# mainV2b.net
KiCad netlist of a schematic drawn in EAGLE
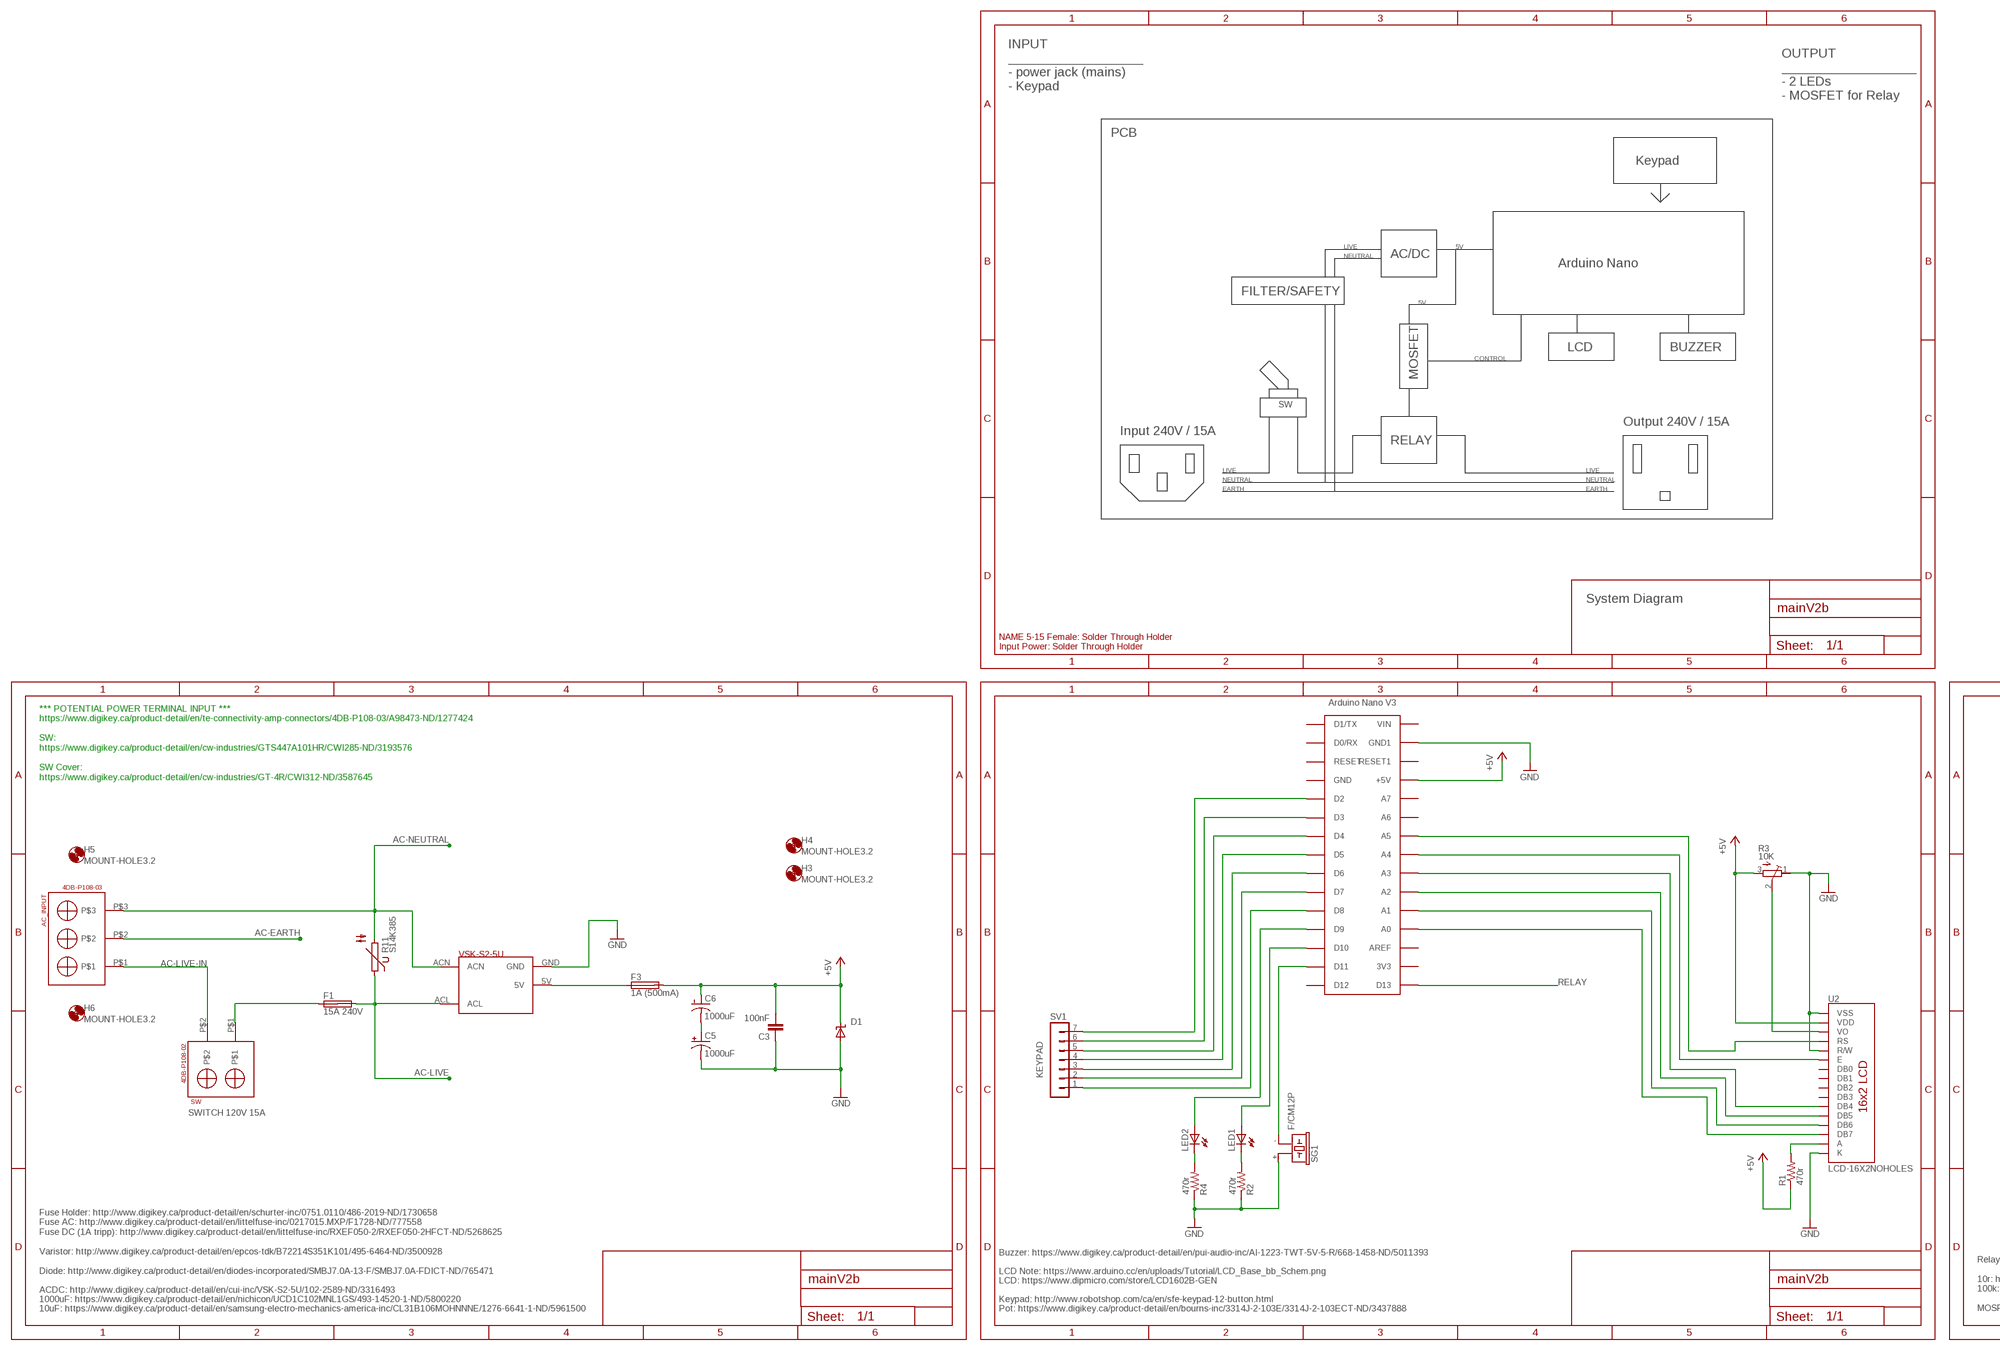
[diagram p0: schematic, sheet 1, part 1 of 2]
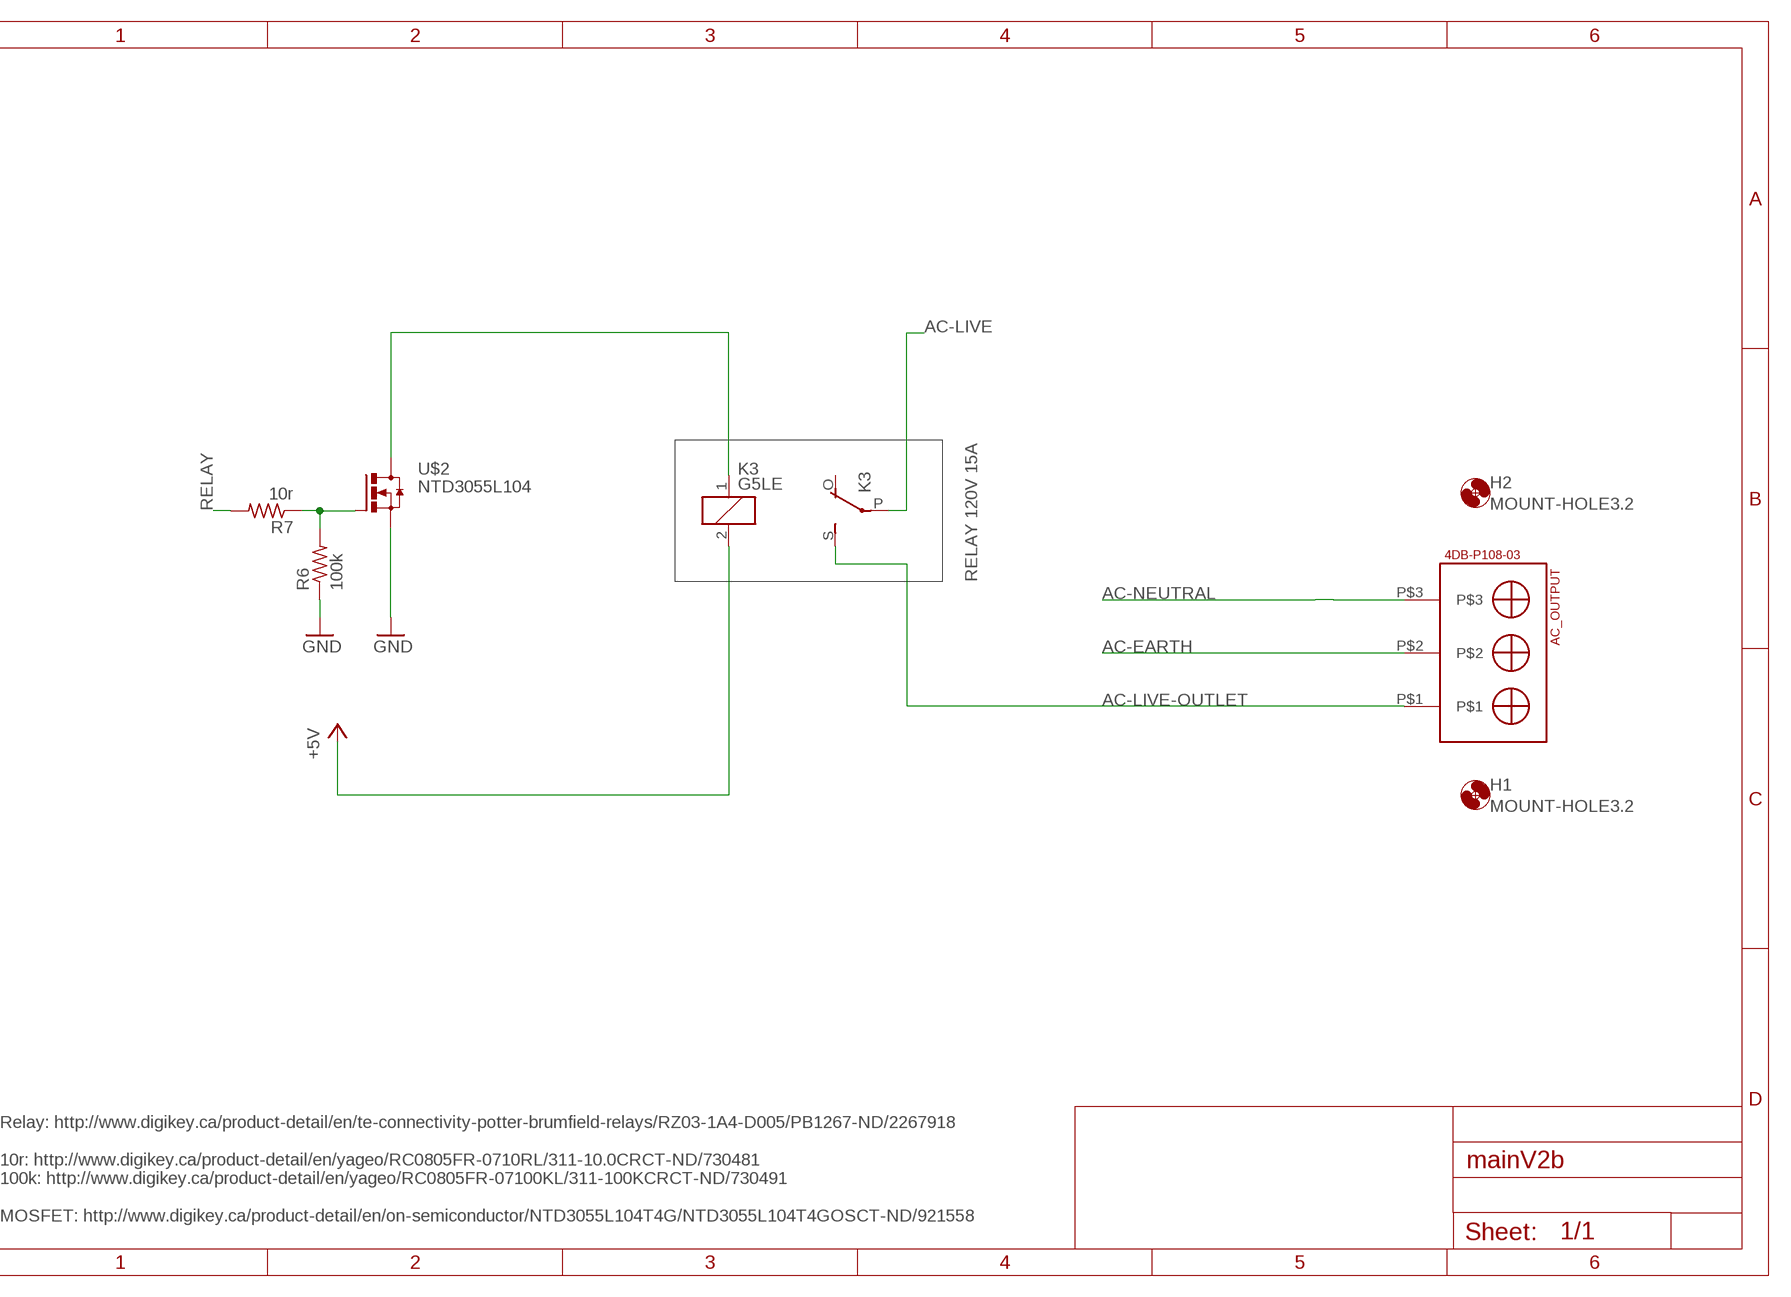
[diagram p1: schematic, sheet 1, part 2 of 2]

(export (version "E")
  (design (tool "Eeschema 10.0.6"))
  (components
    (comp (ref "AC_INPUT")
      (value "4DB-P108-03")
      (footprint "eagle-import:4DB-P108-03")
      (libsource (lib "eagle-import") (part "4DB-P108-03"))
    )
    (comp (ref "AC_OUTPUT")
      (value "4DB-P108-03")
      (footprint "eagle-import:4DB-P108-03")
      (libsource (lib "eagle-import") (part "4DB-P108-03"))
    )
    (comp (ref "C3")
      (value "100nF")
      (footprint "eagle-import:C1206")
      (libsource (lib "eagle-import") (part "C-EUC1206"))
    )
    (comp (ref "C5")
      (value "1000uF")
      (footprint "eagle-import:UD-10X10_NICHICON")
      (libsource (lib "eagle-import") (part "CPOL-USUD-10X10"))
    )
    (comp (ref "C6")
      (value "1000uF")
      (footprint "eagle-import:UD-10X10_NICHICON")
      (libsource (lib "eagle-import") (part "CPOL-USUD-10X10"))
    )
    (comp (ref "D1")
      (value "SUPPRESSOR-SMBJ")
      (footprint "eagle-import:SMBJ")
      (libsource (lib "eagle-import") (part "SUPPRESSOR-SMBJ"))
    )
    (comp (ref "F1")
      (value "15A 240V")
      (footprint "eagle-import:SHK20L")
      (libsource (lib "eagle-import") (part "SHK20L"))
    )
    (comp (ref "F3")
      (value "1A (500mA)")
      (footprint "eagle-import:TE5")
      (libsource (lib "eagle-import") (part "TE5"))
    )
    (comp (ref "H1")
      (value "MOUNT-HOLE3.2")
      (footprint "eagle-import:3,2")
      (libsource (lib "eagle-import") (part "MOUNT-HOLE3.2"))
    )
    (comp (ref "H2")
      (value "MOUNT-HOLE3.2")
      (footprint "eagle-import:3,2")
      (libsource (lib "eagle-import") (part "MOUNT-HOLE3.2"))
    )
    (comp (ref "H3")
      (value "MOUNT-HOLE3.2")
      (footprint "eagle-import:3,2")
      (libsource (lib "eagle-import") (part "MOUNT-HOLE3.2"))
    )
    (comp (ref "H4")
      (value "MOUNT-HOLE3.2")
      (footprint "eagle-import:3,2")
      (libsource (lib "eagle-import") (part "MOUNT-HOLE3.2"))
    )
    (comp (ref "H5")
      (value "MOUNT-HOLE3.2")
      (footprint "eagle-import:3,2")
      (libsource (lib "eagle-import") (part "MOUNT-HOLE3.2"))
    )
    (comp (ref "H6")
      (value "MOUNT-HOLE3.2")
      (footprint "eagle-import:3,2")
      (libsource (lib "eagle-import") (part "MOUNT-HOLE3.2"))
    )
    (comp (ref "K3")
      (value "G5LE")
      (footprint "eagle-import:G5LE")
      (libsource (lib "eagle-import") (part "G5LE"))
    )
    (comp (ref "LED1")
      (value "LEDCHIPLED_1206")
      (footprint "eagle-import:CHIPLED_1206")
      (libsource (lib "eagle-import") (part "LEDCHIPLED_1206"))
    )
    (comp (ref "LED2")
      (value "LEDCHIPLED_1206")
      (footprint "eagle-import:CHIPLED_1206")
      (libsource (lib "eagle-import") (part "LEDCHIPLED_1206"))
    )
    (comp (ref "R1")
      (value "470r")
      (footprint "eagle-import:M2012")
      (libsource (lib "eagle-import") (part "R-US_M2012"))
    )
    (comp (ref "R2")
      (value "470r")
      (footprint "eagle-import:M2012")
      (libsource (lib "eagle-import") (part "R-US_M2012"))
    )
    (comp (ref "R3")
      (value "10K")
      (footprint "eagle-import:RTRIM3314G")
      (libsource (lib "eagle-import") (part "R-TRIMM3314G"))
    )
    (comp (ref "R4")
      (value "470r")
      (footprint "eagle-import:M2012")
      (libsource (lib "eagle-import") (part "R-US_M2012"))
    )
    (comp (ref "R6")
      (value "100k")
      (footprint "eagle-import:M2012")
      (libsource (lib "eagle-import") (part "R-US_M2012"))
    )
    (comp (ref "R7")
      (value "10r")
      (footprint "eagle-import:M2012")
      (libsource (lib "eagle-import") (part "R-US_M2012"))
    )
    (comp (ref "R11")
      (value "S14K385")
      (footprint "eagle-import:S14K385")
      (libsource (lib "eagle-import") (part "S14K385"))
    )
    (comp (ref "SG1")
      (value "F/CM12P")
      (footprint "eagle-import:F_CM12P")
      (libsource (lib "eagle-import") (part "F/CM12P"))
    )
    (comp (ref "SV1")
      (value "MA07-1")
      (footprint "eagle-import:MA07-1")
      (libsource (lib "eagle-import") (part "MA07-1"))
    )
    (comp (ref "SW")
      (value "4DB-P108-02")
      (footprint "eagle-import:4DB-P108-02")
      (libsource (lib "eagle-import") (part "4DB-P108-02"))
    )
    (comp (ref "U$1")
      (value "ARDUINONANO")
      (footprint "eagle-import:PDIP-32")
      (libsource (lib "eagle-import") (part "ARDUINONANO"))
    )
    (comp (ref "U$2")
      (value "NTD3055L104")
      (footprint "eagle-import:NTDV3055L104")
      (libsource (lib "eagle-import") (part "NTD3055L104"))
    )
    (comp (ref "U$4")
      (value "VSK-2S-5U")
      (footprint "eagle-import:VSK-S2-5U")
      (libsource (lib "eagle-import") (part "VSK-2S-5U"))
    )
    (comp (ref "U2")
      (value "LCD-16X2NOHOLES")
      (footprint "eagle-import:LCD-16X2_NOHOLESNOSILK")
      (libsource (lib "eagle-import") (part "LCD-16X2NOHOLES"))
    )
  )
  (nets
    (net (code "1") (name "+5V") (class "Default")
      (node (ref "C3") (pin "2") (pinfunction "2_2") (pintype "passive"))
      (node (ref "C6") (pin "+") (pinfunction "+_+") (pintype "passive"))
      (node (ref "D1") (pin "C") (pinfunction "C_C") (pintype "passive"))
      (node (ref "F3") (pin "2") (pinfunction "2_2") (pintype "passive"))
      (node (ref "K3") (pin "2") (pinfunction "2_2") (pintype "passive"))
      (node (ref "R1") (pin "1") (pinfunction "1_1") (pintype "passive"))
      (node (ref "R3") (pin "3") (pinfunction "A_3") (pintype "passive"))
      (node (ref "U$1") (pin "+5V") (pinfunction "+5V_+5V") (pintype "bidirectional"))
      (node (ref "U2") (pin "2") (pinfunction "VDD_2") (pintype "power_in"))
    )
    (net (code "2") (name "/AC-EARTH") (class "Default")
      (node (ref "AC_INPUT") (pin "P$2") (pinfunction "P$2_P$2") (pintype "bidirectional"))
      (node (ref "AC_OUTPUT") (pin "P$2") (pinfunction "P$2_P$2") (pintype "bidirectional"))
    )
    (net (code "3") (name "/AC-LIVE") (class "Default")
      (node (ref "F1") (pin "2A") (pinfunction "2A_2A") (pintype "passive"))
      (node (ref "K3") (pin "P") (pinfunction "P_P") (pintype "passive"))
      (node (ref "R11") (pin "1") (pinfunction "1_1") (pintype "passive"))
      (node (ref "U$4") (pin "ACL") (pinfunction "ACL_ACL") (pintype "bidirectional"))
    )
    (net (code "4") (name "/AC-LIVE-IN") (class "Default")
      (node (ref "AC_INPUT") (pin "P$1") (pinfunction "P$1_P$1") (pintype "bidirectional"))
      (node (ref "SW") (pin "P$2") (pinfunction "P$2_P$2") (pintype "bidirectional"))
    )
    (net (code "5") (name "/AC-LIVE-OUTLET") (class "Default")
      (node (ref "AC_OUTPUT") (pin "P$1") (pinfunction "P$1_P$1") (pintype "bidirectional"))
      (node (ref "K3") (pin "S") (pinfunction "S_S") (pintype "passive"))
    )
    (net (code "6") (name "/AC-NEUTRAL") (class "Default")
      (node (ref "AC_INPUT") (pin "P$3") (pinfunction "P$3_P$3") (pintype "bidirectional"))
      (node (ref "AC_OUTPUT") (pin "P$3") (pinfunction "P$3_P$3") (pintype "bidirectional"))
      (node (ref "R11") (pin "2") (pinfunction "2_2") (pintype "passive"))
      (node (ref "U$4") (pin "ACN") (pinfunction "ACN_ACN") (pintype "bidirectional"))
    )
    (net (code "7") (name "/RELAY") (class "Default")
      (node (ref "R7") (pin "2") (pinfunction "2_2") (pintype "passive"))
      (node (ref "U$1") (pin "D13") (pinfunction "D13_D13") (pintype "bidirectional"))
    )
    (net (code "8") (name "GND") (class "Default")
      (node (ref "C3") (pin "1") (pinfunction "1_1") (pintype "passive"))
      (node (ref "C5") (pin "-") (pinfunction "-_-") (pintype "passive"))
      (node (ref "D1") (pin "A") (pinfunction "A_A") (pintype "passive"))
      (node (ref "R2") (pin "1") (pinfunction "1_1") (pintype "passive"))
      (node (ref "R3") (pin "1") (pinfunction "E_1") (pintype "passive"))
      (node (ref "R4") (pin "1") (pinfunction "1_1") (pintype "passive"))
      (node (ref "R6") (pin "1") (pinfunction "1_1") (pintype "passive"))
      (node (ref "SG1") (pin "+") (pinfunction "1_+") (pintype "passive"))
      (node (ref "U$1") (pin "GND1") (pinfunction "GND1_GND1") (pintype "bidirectional"))
      (node (ref "U$2") (pin "3") (pinfunction "S_3") (pintype "passive"))
      (node (ref "U$4") (pin "GND") (pinfunction "GND_GND") (pintype "bidirectional"))
      (node (ref "U2") (pin "1") (pinfunction "VSS_1") (pintype "power_in"))
      (node (ref "U2") (pin "16") (pinfunction "K_16") (pintype "power_in"))
      (node (ref "U2") (pin "5") (pinfunction "R/W_5") (pintype "input"))
    )
    (net (code "9") (name "Net-(C5-Pad+)") (class "Default")
      (node (ref "C5") (pin "+") (pinfunction "+_+") (pintype "passive"))
      (node (ref "C6") (pin "-") (pinfunction "-_-") (pintype "passive"))
    )
    (net (code "10") (name "Net-(F1-Pad1A)") (class "Default")
      (node (ref "F1") (pin "1A") (pinfunction "1A_1A") (pintype "passive"))
      (node (ref "SW") (pin "P$1") (pinfunction "P$1_P$1") (pintype "bidirectional"))
    )
    (net (code "11") (name "Net-(F3-Pad1)") (class "Default")
      (node (ref "F3") (pin "1") (pinfunction "1_1") (pintype "passive"))
      (node (ref "U$4") (pin "5V") (pinfunction "5V_5V") (pintype "bidirectional"))
    )
    (net (code "12") (name "Net-(LED1-PadA)") (class "Default")
      (node (ref "LED1") (pin "A") (pinfunction "A_A") (pintype "passive"))
      (node (ref "U$1") (pin "D10") (pinfunction "D10_D10") (pintype "bidirectional"))
    )
    (net (code "13") (name "Net-(LED1-PadC)") (class "Default")
      (node (ref "LED1") (pin "C") (pinfunction "C_C") (pintype "passive"))
      (node (ref "R2") (pin "2") (pinfunction "2_2") (pintype "passive"))
    )
    (net (code "14") (name "Net-(LED2-PadA)") (class "Default")
      (node (ref "LED2") (pin "A") (pinfunction "A_A") (pintype "passive"))
      (node (ref "U$1") (pin "D9") (pinfunction "D9_D9") (pintype "bidirectional"))
    )
    (net (code "15") (name "Net-(LED2-PadC)") (class "Default")
      (node (ref "LED2") (pin "C") (pinfunction "C_C") (pintype "passive"))
      (node (ref "R4") (pin "2") (pinfunction "2_2") (pintype "passive"))
    )
    (net (code "16") (name "Net-(R3-S)") (class "Default")
      (node (ref "R3") (pin "2") (pinfunction "S_2") (pintype "passive"))
      (node (ref "U2") (pin "3") (pinfunction "VO_3") (pintype "bidirectional"))
    )
    (net (code "17") (name "Net-(SG1-2)") (class "Default")
      (node (ref "SG1") (pin "-") (pinfunction "2_-") (pintype "passive"))
      (node (ref "U$1") (pin "D11") (pinfunction "D11_D11") (pintype "bidirectional"))
    )
    (net (code "18") (name "Net-(SV1-Pad1)") (class "Default")
      (node (ref "SV1") (pin "1") (pinfunction "1_1") (pintype "passive"))
      (node (ref "U$1") (pin "D8") (pinfunction "D8_D8") (pintype "bidirectional"))
    )
    (net (code "19") (name "Net-(SV1-Pad2)") (class "Default")
      (node (ref "SV1") (pin "2") (pinfunction "2_2") (pintype "passive"))
      (node (ref "U$1") (pin "D7") (pinfunction "D7_D7") (pintype "bidirectional"))
    )
    (net (code "20") (name "Net-(SV1-Pad3)") (class "Default")
      (node (ref "SV1") (pin "3") (pinfunction "3_3") (pintype "passive"))
      (node (ref "U$1") (pin "D6") (pinfunction "D6_D6") (pintype "bidirectional"))
    )
    (net (code "21") (name "Net-(SV1-Pad4)") (class "Default")
      (node (ref "SV1") (pin "4") (pinfunction "4_4") (pintype "passive"))
      (node (ref "U$1") (pin "D5") (pinfunction "D5_D5") (pintype "bidirectional"))
    )
    (net (code "22") (name "Net-(SV1-Pad5)") (class "Default")
      (node (ref "SV1") (pin "5") (pinfunction "5_5") (pintype "passive"))
      (node (ref "U$1") (pin "D4") (pinfunction "D4_D4") (pintype "bidirectional"))
    )
    (net (code "23") (name "Net-(SV1-Pad6)") (class "Default")
      (node (ref "SV1") (pin "6") (pinfunction "6_6") (pintype "passive"))
      (node (ref "U$1") (pin "D3") (pinfunction "D3_D3") (pintype "bidirectional"))
    )
    (net (code "24") (name "Net-(SV1-Pad7)") (class "Default")
      (node (ref "SV1") (pin "7") (pinfunction "7_7") (pintype "passive"))
      (node (ref "U$1") (pin "D2") (pinfunction "D2_D2") (pintype "bidirectional"))
    )
    (net (code "25") (name "Net-(U$1-A0)") (class "Default")
      (node (ref "U$1") (pin "A7") (pinfunction "A0_A7") (pintype "bidirectional"))
      (node (ref "U2") (pin "14") (pinfunction "DB7_14") (pintype "bidirectional"))
    )
    (net (code "26") (name "Net-(U$1-A1)") (class "Default")
      (node (ref "U$1") (pin "A6") (pinfunction "A1_A6") (pintype "bidirectional"))
      (node (ref "U2") (pin "13") (pinfunction "DB6_13") (pintype "bidirectional"))
    )
    (net (code "27") (name "Net-(U$1-A2)") (class "Default")
      (node (ref "U$1") (pin "A5") (pinfunction "A2_A5") (pintype "bidirectional"))
      (node (ref "U2") (pin "12") (pinfunction "DB5_12") (pintype "bidirectional"))
    )
    (net (code "28") (name "Net-(U$1-A3)") (class "Default")
      (node (ref "U$1") (pin "A4") (pinfunction "A3_A4") (pintype "bidirectional"))
      (node (ref "U2") (pin "11") (pinfunction "DB4_11") (pintype "bidirectional"))
    )
    (net (code "29") (name "Net-(U$1-A4)") (class "Default")
      (node (ref "U$1") (pin "A3") (pinfunction "A4_A3") (pintype "bidirectional"))
      (node (ref "U2") (pin "6") (pinfunction "E_6") (pintype "input"))
    )
    (net (code "30") (name "Net-(U$1-A5)") (class "Default")
      (node (ref "U$1") (pin "A2") (pinfunction "A5_A2") (pintype "bidirectional"))
      (node (ref "U2") (pin "4") (pinfunction "RS_4") (pintype "input"))
    )
    (net (code "31") (name "Net-(U$2-D)") (class "Default")
      (node (ref "K3") (pin "1") (pinfunction "1_1") (pintype "passive"))
      (node (ref "U$2") (pin "4") (pinfunction "D_4") (pintype "passive"))
    )
    (net (code "32") (name "Net-(U$2-G)") (class "Default")
      (node (ref "R6") (pin "2") (pinfunction "2_2") (pintype "passive"))
      (node (ref "R7") (pin "1") (pinfunction "1_1") (pintype "passive"))
      (node (ref "U$2") (pin "1") (pinfunction "G_1") (pintype "passive"))
    )
    (net (code "33") (name "Net-(U2-A)") (class "Default")
      (node (ref "R1") (pin "2") (pinfunction "2_2") (pintype "passive"))
      (node (ref "U2") (pin "15") (pinfunction "A_15") (pintype "power_in"))
    )
    (net (code "34") (name "unconnected-(F1-Pad1B)") (class "Default")
      (node (ref "F1") (pin "1B") (pinfunction "1B_1B") (pintype "passive"))
    )
    (net (code "35") (name "unconnected-(F1-Pad2B)") (class "Default")
      (node (ref "F1") (pin "2B") (pinfunction "2B_2B") (pintype "passive"))
    )
    (net (code "36") (name "unconnected-(K3-PadO)") (class "Default")
      (node (ref "K3") (pin "O") (pinfunction "O_O") (pintype "passive"))
    )
    (net (code "37") (name "unconnected-(U$1-A6-PadA1)") (class "Default")
      (node (ref "U$1") (pin "A1") (pinfunction "A6_A1") (pintype "bidirectional"))
    )
    (net (code "38") (name "unconnected-(U$1-A7-PadA0)") (class "Default")
      (node (ref "U$1") (pin "A0") (pinfunction "A7_A0") (pintype "bidirectional"))
    )
    (net (code "39") (name "unconnected-(U$1-Pad3V3)") (class "Default")
      (node (ref "U$1") (pin "3V3") (pinfunction "3V3_3V3") (pintype "bidirectional"))
    )
    (net (code "40") (name "unconnected-(U$1-PadAREF)") (class "Default")
      (node (ref "U$1") (pin "AREF") (pinfunction "AREF_AREF") (pintype "bidirectional"))
    )
    (net (code "41") (name "unconnected-(U$1-PadD0{slash}RX)") (class "Default")
      (node (ref "U$1") (pin "D0/RX") (pinfunction "D0/RX_D0/RX") (pintype "bidirectional"))
    )
    (net (code "42") (name "unconnected-(U$1-PadD1{slash}TX)") (class "Default")
      (node (ref "U$1") (pin "D1/TX") (pinfunction "D1/TX_D1/TX") (pintype "bidirectional"))
    )
    (net (code "43") (name "unconnected-(U$1-PadD12)") (class "Default")
      (node (ref "U$1") (pin "D12") (pinfunction "D12_D12") (pintype "bidirectional"))
    )
    (net (code "44") (name "unconnected-(U$1-PadGND)") (class "Default")
      (node (ref "U$1") (pin "GND") (pinfunction "GND_GND") (pintype "bidirectional"))
    )
    (net (code "45") (name "unconnected-(U$1-PadRESET)") (class "Default")
      (node (ref "U$1") (pin "RESET") (pinfunction "RESET_RESET") (pintype "bidirectional"))
    )
    (net (code "46") (name "unconnected-(U$1-PadRESET1)") (class "Default")
      (node (ref "U$1") (pin "RESET1") (pinfunction "RESET1_RESET1") (pintype "bidirectional"))
    )
    (net (code "47") (name "unconnected-(U$1-PadVIN)") (class "Default")
      (node (ref "U$1") (pin "VIN") (pinfunction "VIN_VIN") (pintype "bidirectional"))
    )
    (net (code "48") (name "unconnected-(U2-DB0-Pad7)") (class "Default")
      (node (ref "U2") (pin "7") (pinfunction "DB0_7") (pintype "bidirectional"))
    )
    (net (code "49") (name "unconnected-(U2-DB1-Pad8)") (class "Default")
      (node (ref "U2") (pin "8") (pinfunction "DB1_8") (pintype "bidirectional"))
    )
    (net (code "50") (name "unconnected-(U2-DB2-Pad9)") (class "Default")
      (node (ref "U2") (pin "9") (pinfunction "DB2_9") (pintype "bidirectional"))
    )
    (net (code "51") (name "unconnected-(U2-DB3-Pad10)") (class "Default")
      (node (ref "U2") (pin "10") (pinfunction "DB3_10") (pintype "bidirectional"))
    )
  )
)
